# AuxChannels.net
KiCad netlist of a schematic drawn in Altium Designer
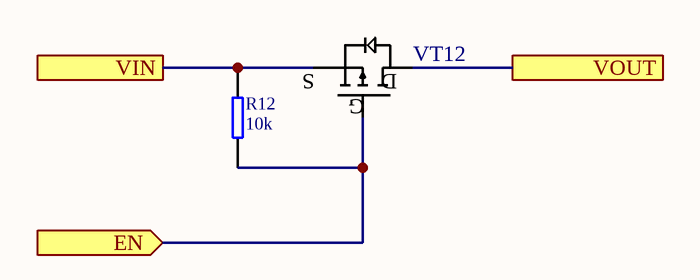
[diagram p0: AuxChannels.SchDoc]

(export (version "E")
  (design (tool "Eeschema 10.0.6"))
  (components
    (comp (ref "R12")
      (value "10k")
      (footprint "RES 0402")
      (description "Resistor")
      (fields (field (name "Comment") "RES 0402 10k"))
      (libsource (lib "!main") (part "!Resistor"))
    )
    (comp (ref "VT12")
      (value "!Generic P MOSFET")
      (footprint "DFN-8_3x3")
      (description "generic P mosfet")
      (libsource (lib "transistors") (part "!Generic P MOSFET"))
    )
  )
  (nets
    (net (code "1") (name "/EN") (class "Default")
      (node (ref "R12") (pin "1") (pinfunction "11_1") (pintype "passive"))
      (node (ref "VT12") (pin "G2") (pintype "passive"))
    )
    (net (code "2") (name "/VIN") (class "Default")
      (node (ref "R12") (pin "2") (pinfunction "12_2") (pintype "passive"))
      (node (ref "VT12") (pin "S1") (pintype "passive"))
    )
    (net (code "3") (name "/VOUT") (class "Default") (node (ref "VT12") (pin "D1") (pintype "passive")))
  )
)
